# Motor_Drivers.net
KiCad netlist of a schematic drawn in Altium Designer
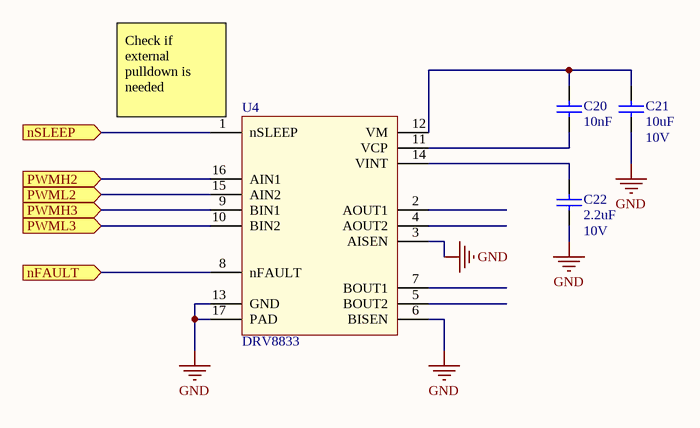
[diagram p0: Motor Drivers.SchDoc]

(export (version "E")
  (design (tool "Eeschema 10.0.6"))
  (components
    (comp (ref "C20")
      (value "10nF")
      (footprint "CAPC1608L")
      (description "CAP CER 10nF X7R +-10% 50V 0603")
      (libsource (lib "ECE AD19Components_19V1") (part "CC_10nF_0603"))
    )
    (comp (ref "C21")
      (value "10uF")
      (footprint "CAPC2012L")
      (description "CAP CER 10uF X7R +-20% 10V 0805")
      (fields (field (name "MAX VOLTAGE") "10V"))
      (libsource (lib "ECE AD19Components_19V1") (part "CC_10uF_0805_10V"))
    )
    (comp (ref "C22")
      (value "2.2uF")
      (footprint "CAPC1608L")
      (description "CAP CER 2.2uF X5R +-20% 10V 0603")
      (fields (field (name "MAX VOLTAGE") "10V"))
      (libsource (lib "ECE AD19Components_19V1") (part "CC_2.2uF_0603"))
    )
    (comp (ref "U4")
      (value "DRV8833")
      (footprint "HTSOP16")
      (description "Dual H-Bridge Motor Driver 1.5A")
      (libsource (lib "ENCE461AD19_19V2") (part "DRV8833"))
    )
  )
  (nets
    (net (code "1") (name "/PWMH2") (class "Default")
      (node (ref "U4") (pin "16") (pinfunction "AIN1_16") (pintype "passive"))
    )
    (net (code "2") (name "/PWMH3") (class "Default")
      (node (ref "U4") (pin "9") (pinfunction "BIN1_9") (pintype "passive"))
    )
    (net (code "3") (name "/PWML2") (class "Default")
      (node (ref "U4") (pin "15") (pinfunction "AIN2_15") (pintype "passive"))
    )
    (net (code "4") (name "/PWML3") (class "Default")
      (node (ref "U4") (pin "10") (pinfunction "BIN2_10") (pintype "passive"))
    )
    (net (code "5") (name "/nFAULT") (class "Default")
      (node (ref "U4") (pin "8") (pinfunction "nFAULT_8") (pintype "passive"))
    )
    (net (code "6") (name "/nSLEEP") (class "Default")
      (node (ref "U4") (pin "1") (pinfunction "nSLEEP_1") (pintype "passive"))
    )
    (net (code "7") (name "GND") (class "Default")
      (node (ref "C21") (pin "1") (pinfunction "1_1") (pintype "passive"))
      (node (ref "C22") (pin "1") (pinfunction "1_1") (pintype "passive"))
      (node (ref "U4") (pin "13") (pinfunction "GND_13") (pintype "passive"))
      (node (ref "U4") (pin "17") (pinfunction "PAD_17") (pintype "passive"))
      (node (ref "U4") (pin "3") (pinfunction "AISEN_3") (pintype "passive"))
      (node (ref "U4") (pin "6") (pinfunction "BISEN_6") (pintype "passive"))
    )
    (net (code "8") (name "Net-(U4-VCP)") (class "Default")
      (node (ref "C20") (pin "1") (pinfunction "1_1") (pintype "passive"))
      (node (ref "U4") (pin "11") (pinfunction "VCP_11") (pintype "passive"))
    )
    (net (code "9") (name "Net-(U4-VINT)") (class "Default")
      (node (ref "C22") (pin "2") (pinfunction "2_2") (pintype "passive"))
      (node (ref "U4") (pin "14") (pinfunction "VINT_14") (pintype "passive"))
    )
    (net (code "10") (name "Net-(U4-VM)") (class "Default")
      (node (ref "C20") (pin "2") (pinfunction "2_2") (pintype "passive"))
      (node (ref "C21") (pin "2") (pinfunction "2_2") (pintype "passive"))
      (node (ref "U4") (pin "12") (pinfunction "VM_12") (pintype "passive"))
    )
    (net (code "11") (name "unconnected-(U4-AOUT1-Pad2)") (class "Default")
      (node (ref "U4") (pin "2") (pinfunction "AOUT1_2") (pintype "passive"))
    )
    (net (code "12") (name "unconnected-(U4-AOUT2-Pad4)") (class "Default")
      (node (ref "U4") (pin "4") (pinfunction "AOUT2_4") (pintype "passive"))
    )
    (net (code "13") (name "unconnected-(U4-BOUT1-Pad7)") (class "Default")
      (node (ref "U4") (pin "7") (pinfunction "BOUT1_7") (pintype "passive"))
    )
    (net (code "14") (name "unconnected-(U4-BOUT2-Pad5)") (class "Default")
      (node (ref "U4") (pin "5") (pinfunction "BOUT2_5") (pintype "passive"))
    )
  )
)
